# motor.net
KiCad netlist of a schematic drawn in Altium Designer
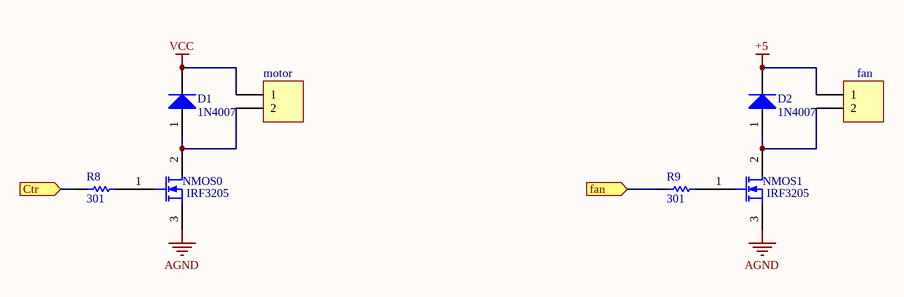
[diagram p0: motor.SchDoc]

(export (version "E")
  (design (tool "Eeschema 10.0.6"))
  (components
    (comp (ref "D1")
      (value "1N4007")
      (footprint "SMA(M)")
      (description "整流二极管")
      (libsource (lib "Self Establish") (part "Diode1"))
    )
    (comp (ref "D2")
      (value "1N4007")
      (footprint "SMA(M)")
      (description "整流二极管")
      (libsource (lib "Self Establish") (part "Diode1"))
    )
    (comp (ref "NMOS0")
      (value "IRF3205")
      (footprint "TO-263-3(M)")
      (libsource (lib "Self Establish") (part "MOSFET-N"))
    )
    (comp (ref "NMOS1")
      (value "IRF3205")
      (footprint "TO-263-3(M)")
      (libsource (lib "Self Establish") (part "MOSFET-N"))
    )
    (comp (ref "R8")
      (value "301")
      (footprint "0805(M)")
      (fields (field (name "Comment") "Res"))
      (libsource (lib "Self Establish") (part "Res"))
    )
    (comp (ref "R9")
      (value "301")
      (footprint "0805(M)")
      (fields (field (name "Comment") "Res"))
      (libsource (lib "Self Establish") (part "Res"))
    )
    (comp (ref "Ter0")
      (value "motor")
      (footprint "KF301-2P(DIP)")
      (description "接线端子 脚距5.08MM 300V/16A")
      (libsource (lib "Self Establish") (part "KF301-2P"))
    )
    (comp (ref "Ter1")
      (value "fan")
      (footprint "KF301-2P(DIP)")
      (description "接线端子 脚距5.08MM 300V/16A")
      (libsource (lib "Self Establish") (part "KF301-2P"))
    )
  )
  (nets
    (net (code "1") (name "+5") (class "Default")
      (node (ref "D2") (pin "2") (pinfunction "N_2") (pintype "passive"))
      (node (ref "Ter1") (pin "1") (pinfunction "1_1") (pintype "passive"))
    )
    (net (code "2") (name "/Ctr") (class "Default")
      (node (ref "R8") (pin "1") (pinfunction "1_1") (pintype "passive"))
    )
    (net (code "3") (name "/fan") (class "Default")
      (node (ref "R9") (pin "1") (pinfunction "1_1") (pintype "passive"))
    )
    (net (code "4") (name "AGND") (class "Default")
      (node (ref "NMOS0") (pin "3") (pinfunction "S_3") (pintype "passive"))
      (node (ref "NMOS1") (pin "3") (pinfunction "S_3") (pintype "passive"))
    )
    (net (code "5") (name "Net-(D1-P)") (class "Default")
      (node (ref "D1") (pin "1") (pinfunction "P_1") (pintype "passive"))
      (node (ref "NMOS0") (pin "2") (pinfunction "D_2") (pintype "passive"))
      (node (ref "Ter0") (pin "2") (pinfunction "2_2") (pintype "passive"))
    )
    (net (code "6") (name "Net-(D2-P)") (class "Default")
      (node (ref "D2") (pin "1") (pinfunction "P_1") (pintype "passive"))
      (node (ref "NMOS1") (pin "2") (pinfunction "D_2") (pintype "passive"))
      (node (ref "Ter1") (pin "2") (pinfunction "2_2") (pintype "passive"))
    )
    (net (code "7") (name "Net-(NMOS0-G)") (class "Default")
      (node (ref "NMOS0") (pin "1") (pinfunction "G_1") (pintype "passive"))
      (node (ref "R8") (pin "2") (pinfunction "2_2") (pintype "passive"))
    )
    (net (code "8") (name "Net-(NMOS1-G)") (class "Default")
      (node (ref "NMOS1") (pin "1") (pinfunction "G_1") (pintype "passive"))
      (node (ref "R9") (pin "2") (pinfunction "2_2") (pintype "passive"))
    )
    (net (code "9") (name "VCC") (class "Default")
      (node (ref "D1") (pin "2") (pinfunction "N_2") (pintype "passive"))
      (node (ref "Ter0") (pin "1") (pinfunction "1_1") (pintype "passive"))
    )
  )
)
